# tick-mk-4_1.net
KiCad netlist of a schematic drawn in EAGLE
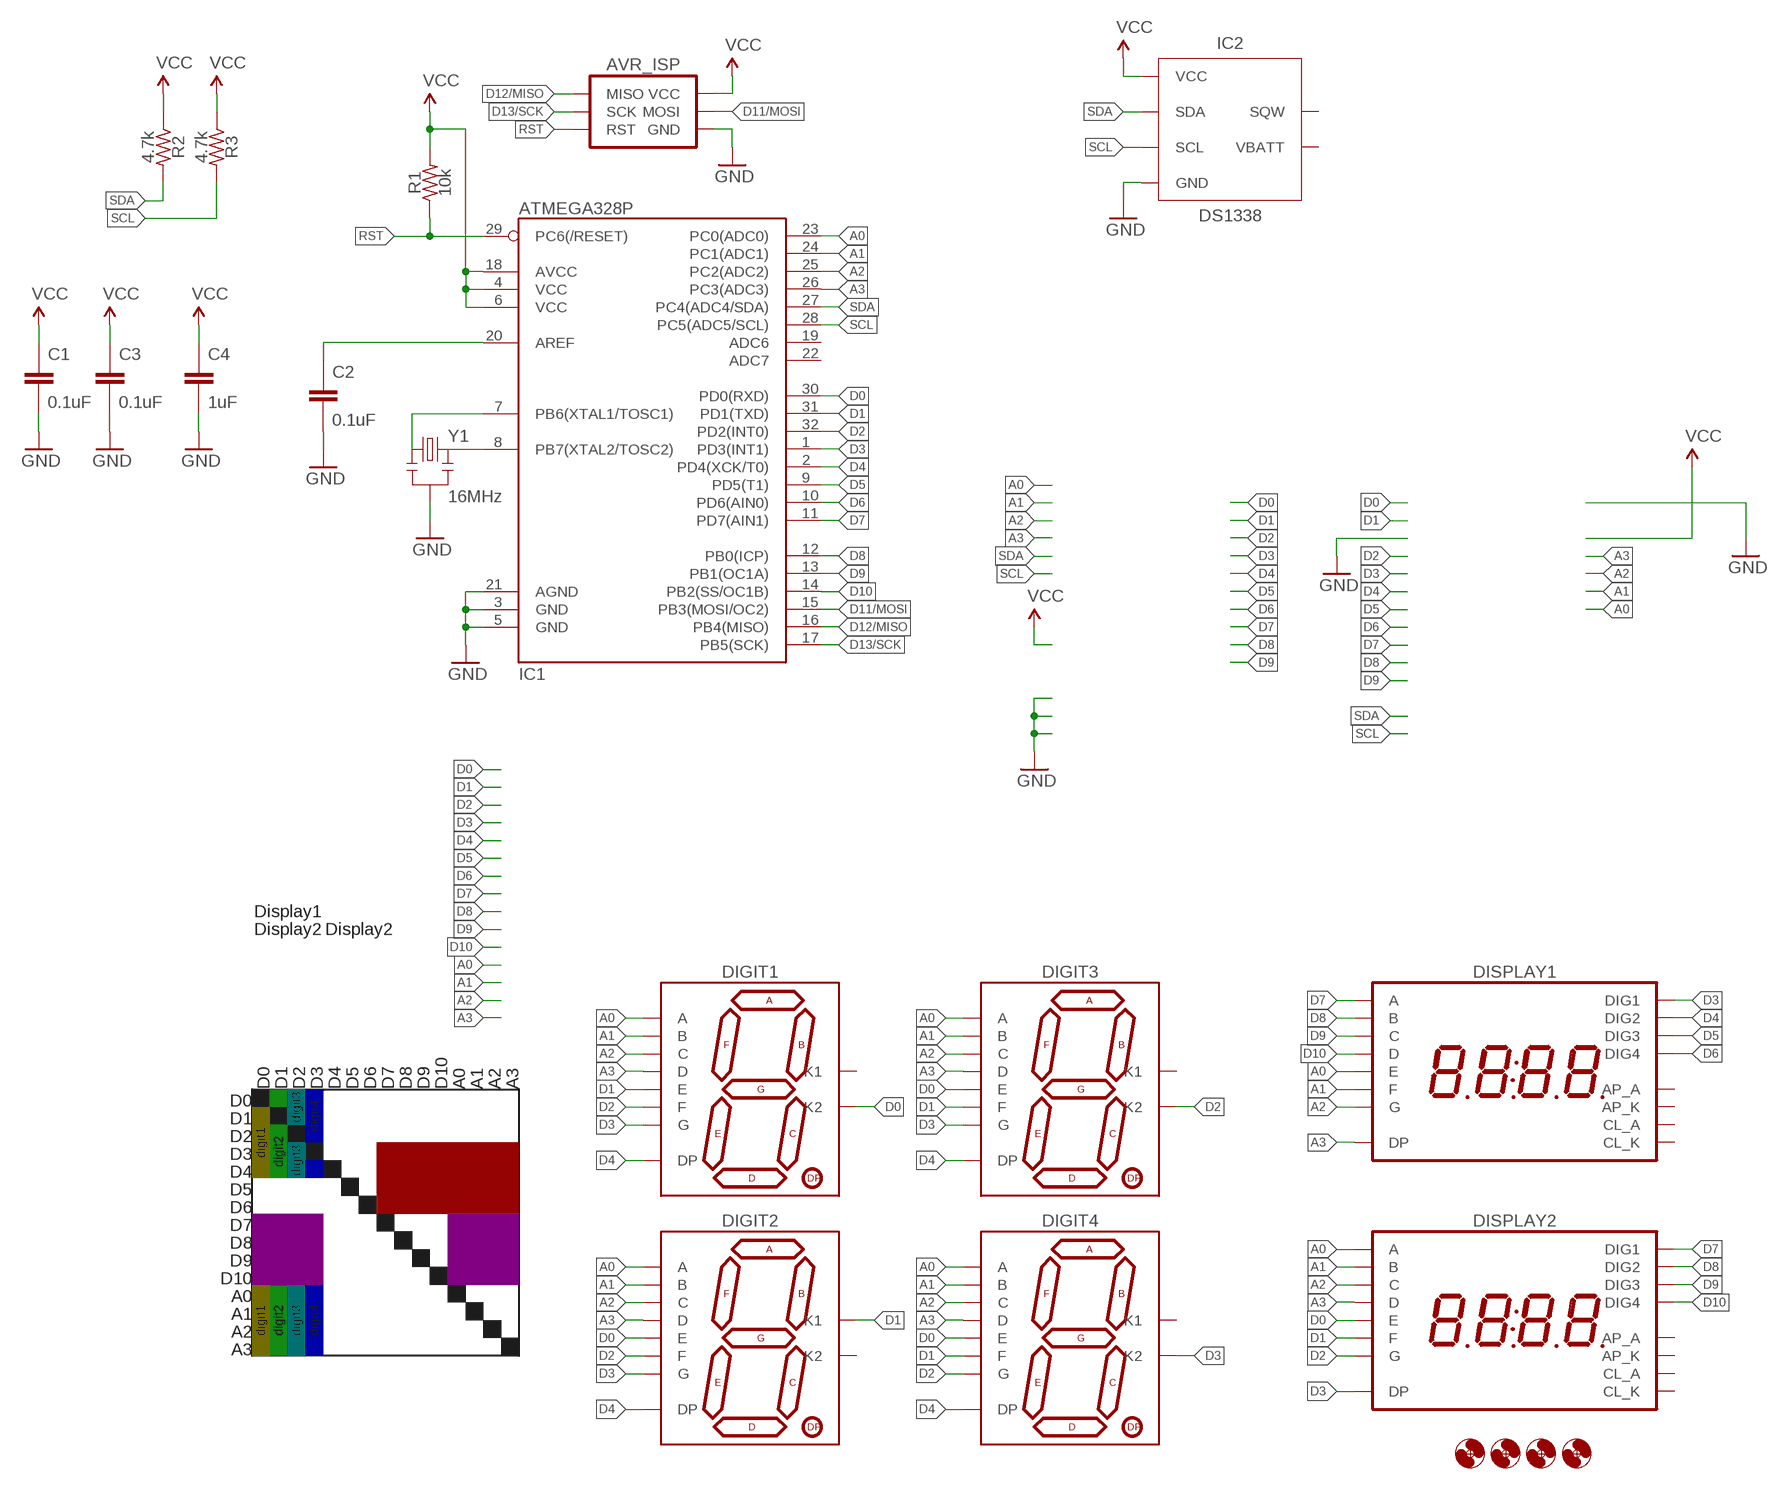
[diagram p0: schematic, sheet 1]

(export (version "E")
  (design (tool "Eeschema 10.0.6"))
  (components
    (comp (ref "AVR_ISP")
      (value "AVR_SPI_PRG_6PTH")
      (footprint "eagle-import:2X3")
      (libsource (lib "eagle-import") (part "AVR_SPI_PRG_6PTH"))
    )
    (comp (ref "C1")
      (value "0.1uF")
      (footprint "eagle-import:C0805")
      (libsource (lib "eagle-import") (part "CAPACITOR-CERAMICC0805"))
    )
    (comp (ref "C2")
      (value "0.1uF")
      (footprint "eagle-import:C0805")
      (libsource (lib "eagle-import") (part "CAPACITOR-CERAMICC0805"))
    )
    (comp (ref "C3")
      (value "0.1uF")
      (footprint "eagle-import:C0805")
      (libsource (lib "eagle-import") (part "CAPACITOR-CERAMICC0805"))
    )
    (comp (ref "C4")
      (value "1uF")
      (footprint "eagle-import:C0805")
      (libsource (lib "eagle-import") (part "CAPACITOR-CERAMICC0805"))
    )
    (comp (ref "DIGIT1")
      (value "7SEG_1DIGPTH-25.4MM")
      (footprint "eagle-import:7SEG_1DIG_25.4MM")
      (libsource (lib "eagle-import") (part "7SEG_1DIGPTH-25.4MM"))
    )
    (comp (ref "DIGIT2")
      (value "7SEG_1DIGPTH-25.4MM")
      (footprint "eagle-import:7SEG_1DIG_25.4MM")
      (libsource (lib "eagle-import") (part "7SEG_1DIGPTH-25.4MM"))
    )
    (comp (ref "DIGIT3")
      (value "7SEG_1DIGPTH-25.4MM")
      (footprint "eagle-import:7SEG_1DIG_25.4MM")
      (libsource (lib "eagle-import") (part "7SEG_1DIGPTH-25.4MM"))
    )
    (comp (ref "DIGIT4")
      (value "7SEG_1DIGPTH-25.4MM")
      (footprint "eagle-import:7SEG_1DIG_25.4MM")
      (libsource (lib "eagle-import") (part "7SEG_1DIGPTH-25.4MM"))
    )
    (comp (ref "DISPLAY1")
      (value "7SEG_4DIGIT_COLON_APOS")
      (footprint "eagle-import:7SEG_4DIG_10MM")
      (libsource (lib "eagle-import") (part "7SEG_4DIGIT_COLON_APOS"))
    )
    (comp (ref "DISPLAY2")
      (value "7SEG_4DIGIT_COLON_APOS")
      (footprint "eagle-import:7SEG_4DIG_10MM")
      (libsource (lib "eagle-import") (part "7SEG_4DIGIT_COLON_APOS"))
    )
    (comp (ref "H1")
      (value "HOLE#2")
      (footprint "eagle-import:HOLE-#2")
      (libsource (lib "eagle-import") (part "HOLE#2"))
    )
    (comp (ref "H2")
      (value "HOLE#2")
      (footprint "eagle-import:HOLE-#2")
      (libsource (lib "eagle-import") (part "HOLE#2"))
    )
    (comp (ref "H3")
      (value "HOLE#2")
      (footprint "eagle-import:HOLE-#2")
      (libsource (lib "eagle-import") (part "HOLE#2"))
    )
    (comp (ref "H4")
      (value "HOLE#2")
      (footprint "eagle-import:HOLE-#2")
      (libsource (lib "eagle-import") (part "HOLE#2"))
    )
    (comp (ref "IC1")
      (value "ATMEGA328P")
      (footprint "eagle-import:TQFP32-08")
      (libsource (lib "eagle-import") (part "ATMEGA328_SMT"))
    )
    (comp (ref "IC2")
      (value "DS1338")
      (footprint "eagle-import:SO16W")
      (libsource (lib "eagle-import") (part "DS1338CSOIC16W"))
    )
    (comp (ref "R1")
      (value "10k")
      (footprint "eagle-import:R0805")
      (libsource (lib "eagle-import") (part "RESISTORR0805"))
    )
    (comp (ref "R2")
      (value "4.7k")
      (footprint "eagle-import:R0805")
      (libsource (lib "eagle-import") (part "RESISTORR0805"))
    )
    (comp (ref "R3")
      (value "4.7k")
      (footprint "eagle-import:R0805")
      (libsource (lib "eagle-import") (part "RESISTORR0805"))
    )
    (comp (ref "Y1")
      (value "16MHz")
      (footprint "eagle-import:RESONATOR-4.7X4.1X1.2MM")
      (libsource (lib "eagle-import") (part "RESONATORSMD-4.7X4.1X1.2"))
    )
  )
  (nets
    (net (code "1") (name "A0") (class "Default")
      (node (ref "DIGIT1") (pin "7") (pinfunction "A_7") (pintype "bidirectional"))
      (node (ref "DIGIT2") (pin "7") (pinfunction "A_7") (pintype "bidirectional"))
      (node (ref "DIGIT3") (pin "7") (pinfunction "A_7") (pintype "bidirectional"))
      (node (ref "DIGIT4") (pin "7") (pinfunction "A_7") (pintype "bidirectional"))
      (node (ref "DISPLAY1") (pin "5") (pinfunction "E_5") (pintype "passive"))
      (node (ref "DISPLAY2") (pin "14") (pinfunction "A_14") (pintype "passive"))
      (node (ref "IC1") (pin "23") (pinfunction "PC0(ADC0)_23") (pintype "bidirectional"))
    )
    (net (code "2") (name "A1") (class "Default")
      (node (ref "DIGIT1") (pin "6") (pinfunction "B_6") (pintype "bidirectional"))
      (node (ref "DIGIT2") (pin "6") (pinfunction "B_6") (pintype "bidirectional"))
      (node (ref "DIGIT3") (pin "6") (pinfunction "B_6") (pintype "bidirectional"))
      (node (ref "DIGIT4") (pin "6") (pinfunction "B_6") (pintype "bidirectional"))
      (node (ref "DISPLAY1") (pin "11") (pinfunction "F_11") (pintype "passive"))
      (node (ref "DISPLAY2") (pin "16") (pinfunction "B_16") (pintype "passive"))
      (node (ref "IC1") (pin "24") (pinfunction "PC1(ADC1)_24") (pintype "bidirectional"))
    )
    (net (code "3") (name "A2") (class "Default")
      (node (ref "DIGIT1") (pin "4") (pinfunction "C_4") (pintype "bidirectional"))
      (node (ref "DIGIT2") (pin "4") (pinfunction "C_4") (pintype "bidirectional"))
      (node (ref "DIGIT3") (pin "4") (pinfunction "C_4") (pintype "bidirectional"))
      (node (ref "DIGIT4") (pin "4") (pinfunction "C_4") (pintype "bidirectional"))
      (node (ref "DISPLAY1") (pin "15") (pinfunction "G_15") (pintype "passive"))
      (node (ref "DISPLAY2") (pin "13") (pinfunction "C_13") (pintype "passive"))
      (node (ref "IC1") (pin "25") (pinfunction "PC2(ADC2)_25") (pintype "bidirectional"))
    )
    (net (code "4") (name "A3") (class "Default")
      (node (ref "DIGIT1") (pin "2") (pinfunction "D_2") (pintype "bidirectional"))
      (node (ref "DIGIT2") (pin "2") (pinfunction "D_2") (pintype "bidirectional"))
      (node (ref "DIGIT3") (pin "2") (pinfunction "D_2") (pintype "bidirectional"))
      (node (ref "DIGIT4") (pin "2") (pinfunction "D_2") (pintype "bidirectional"))
      (node (ref "DISPLAY1") (pin "7") (pinfunction "DP_7") (pintype "passive"))
      (node (ref "DISPLAY2") (pin "3") (pinfunction "D_3") (pintype "passive"))
      (node (ref "IC1") (pin "26") (pinfunction "PC3(ADC3)_26") (pintype "bidirectional"))
    )
    (net (code "5") (name "D0") (class "Default")
      (node (ref "DIGIT1") (pin "8") (pinfunction "K2_8") (pintype "bidirectional"))
      (node (ref "DIGIT2") (pin "1") (pinfunction "E_1") (pintype "bidirectional"))
      (node (ref "DIGIT3") (pin "1") (pinfunction "E_1") (pintype "bidirectional"))
      (node (ref "DIGIT4") (pin "1") (pinfunction "E_1") (pintype "bidirectional"))
      (node (ref "DISPLAY2") (pin "5") (pinfunction "E_5") (pintype "passive"))
      (node (ref "IC1") (pin "30") (pinfunction "PD0(RXD)_30") (pintype "bidirectional"))
    )
    (net (code "6") (name "D1") (class "Default")
      (node (ref "DIGIT1") (pin "1") (pinfunction "E_1") (pintype "bidirectional"))
      (node (ref "DIGIT2") (pin "3") (pinfunction "K1_3") (pintype "bidirectional"))
      (node (ref "DIGIT3") (pin "9") (pinfunction "F_9") (pintype "bidirectional"))
      (node (ref "DIGIT4") (pin "9") (pinfunction "F_9") (pintype "bidirectional"))
      (node (ref "DISPLAY2") (pin "11") (pinfunction "F_11") (pintype "passive"))
      (node (ref "IC1") (pin "31") (pinfunction "PD1(TXD)_31") (pintype "bidirectional"))
    )
    (net (code "7") (name "D2") (class "Default")
      (node (ref "DIGIT1") (pin "9") (pinfunction "F_9") (pintype "bidirectional"))
      (node (ref "DIGIT2") (pin "9") (pinfunction "F_9") (pintype "bidirectional"))
      (node (ref "DIGIT3") (pin "8") (pinfunction "K2_8") (pintype "bidirectional"))
      (node (ref "DIGIT4") (pin "10") (pinfunction "G_10") (pintype "bidirectional"))
      (node (ref "DISPLAY2") (pin "15") (pinfunction "G_15") (pintype "passive"))
      (node (ref "IC1") (pin "32") (pinfunction "PD2(INT0)_32") (pintype "bidirectional"))
    )
    (net (code "8") (name "D3") (class "Default")
      (node (ref "DIGIT1") (pin "10") (pinfunction "G_10") (pintype "bidirectional"))
      (node (ref "DIGIT2") (pin "10") (pinfunction "G_10") (pintype "bidirectional"))
      (node (ref "DIGIT3") (pin "10") (pinfunction "G_10") (pintype "bidirectional"))
      (node (ref "DIGIT4") (pin "8") (pinfunction "K2_8") (pintype "bidirectional"))
      (node (ref "DISPLAY1") (pin "1") (pinfunction "DIG1_1") (pintype "passive"))
      (node (ref "DISPLAY2") (pin "7") (pinfunction "DP_7") (pintype "passive"))
      (node (ref "IC1") (pin "1") (pinfunction "PD3(INT1)_1") (pintype "bidirectional"))
    )
    (net (code "9") (name "D4") (class "Default")
      (node (ref "DIGIT1") (pin "5") (pinfunction "DP_5") (pintype "bidirectional"))
      (node (ref "DIGIT2") (pin "5") (pinfunction "DP_5") (pintype "bidirectional"))
      (node (ref "DIGIT3") (pin "5") (pinfunction "DP_5") (pintype "bidirectional"))
      (node (ref "DIGIT4") (pin "5") (pinfunction "DP_5") (pintype "bidirectional"))
      (node (ref "DISPLAY1") (pin "2") (pinfunction "DIG2_2") (pintype "passive"))
      (node (ref "IC1") (pin "2") (pinfunction "PD4(XCK/T0)_2") (pintype "bidirectional"))
    )
    (net (code "10") (name "D5") (class "Default")
      (node (ref "DISPLAY1") (pin "6") (pinfunction "DIG3_6") (pintype "passive"))
      (node (ref "IC1") (pin "9") (pinfunction "PD5(T1)_9") (pintype "bidirectional"))
    )
    (net (code "11") (name "D6") (class "Default")
      (node (ref "DISPLAY1") (pin "8") (pinfunction "DIG4_8") (pintype "passive"))
      (node (ref "IC1") (pin "10") (pinfunction "PD6(AIN0)_10") (pintype "bidirectional"))
    )
    (net (code "12") (name "D7") (class "Default")
      (node (ref "DISPLAY1") (pin "14") (pinfunction "A_14") (pintype "passive"))
      (node (ref "DISPLAY2") (pin "1") (pinfunction "DIG1_1") (pintype "passive"))
      (node (ref "IC1") (pin "11") (pinfunction "PD7(AIN1)_11") (pintype "bidirectional"))
    )
    (net (code "13") (name "D8") (class "Default")
      (node (ref "DISPLAY1") (pin "16") (pinfunction "B_16") (pintype "passive"))
      (node (ref "DISPLAY2") (pin "2") (pinfunction "DIG2_2") (pintype "passive"))
      (node (ref "IC1") (pin "12") (pinfunction "PB0(ICP)_12") (pintype "bidirectional"))
    )
    (net (code "14") (name "D9") (class "Default")
      (node (ref "DISPLAY1") (pin "13") (pinfunction "C_13") (pintype "passive"))
      (node (ref "DISPLAY2") (pin "6") (pinfunction "DIG3_6") (pintype "passive"))
      (node (ref "IC1") (pin "13") (pinfunction "PB1(OC1A)_13") (pintype "bidirectional"))
    )
    (net (code "15") (name "D10") (class "Default")
      (node (ref "DISPLAY1") (pin "3") (pinfunction "D_3") (pintype "passive"))
      (node (ref "DISPLAY2") (pin "8") (pinfunction "DIG4_8") (pintype "passive"))
      (node (ref "IC1") (pin "14") (pinfunction "PB2(SS/OC1B)_14") (pintype "bidirectional"))
    )
    (net (code "16") (name "D11{slash}MOSI") (class "Default")
      (node (ref "AVR_ISP") (pin "4") (pinfunction "MOSI_4") (pintype "passive"))
      (node (ref "IC1") (pin "15") (pinfunction "PB3(MOSI/OC2)_15") (pintype "bidirectional"))
    )
    (net (code "17") (name "D12{slash}MISO") (class "Default")
      (node (ref "AVR_ISP") (pin "1") (pinfunction "MISO_1") (pintype "passive"))
      (node (ref "IC1") (pin "16") (pinfunction "PB4(MISO)_16") (pintype "bidirectional"))
    )
    (net (code "18") (name "D13{slash}SCK") (class "Default")
      (node (ref "AVR_ISP") (pin "3") (pinfunction "SCK_3") (pintype "passive"))
      (node (ref "IC1") (pin "17") (pinfunction "PB5(SCK)_17") (pintype "bidirectional"))
    )
    (net (code "19") (name "GND") (class "Default")
      (node (ref "AVR_ISP") (pin "6") (pinfunction "GND_6") (pintype "passive"))
      (node (ref "C1") (pin "2") (pinfunction "2_2") (pintype "passive"))
      (node (ref "C2") (pin "2") (pinfunction "2_2") (pintype "passive"))
      (node (ref "C3") (pin "2") (pinfunction "2_2") (pintype "passive"))
      (node (ref "C4") (pin "2") (pinfunction "2_2") (pintype "passive"))
      (node (ref "IC1") (pin "21") (pinfunction "AGND_21") (pintype "bidirectional"))
      (node (ref "IC1") (pin "3") (pinfunction "GND_3") (pintype "bidirectional"))
      (node (ref "IC1") (pin "5") (pinfunction "GND_5") (pintype "bidirectional"))
      (node (ref "IC2") (pin "10") (pinfunction "GND_10") (pintype "bidirectional"))
      (node (ref "IC2") (pin "11") (pinfunction "GND_11") (pintype "bidirectional"))
      (node (ref "IC2") (pin "12") (pinfunction "GND_12") (pintype "bidirectional"))
      (node (ref "IC2") (pin "13") (pinfunction "GND_13") (pintype "bidirectional"))
      (node (ref "IC2") (pin "15") (pinfunction "GND_15") (pintype "bidirectional"))
      (node (ref "IC2") (pin "4") (pinfunction "GND_4") (pintype "bidirectional"))
      (node (ref "IC2") (pin "5") (pinfunction "GND_5") (pintype "bidirectional"))
      (node (ref "IC2") (pin "6") (pinfunction "GND_6") (pintype "bidirectional"))
      (node (ref "IC2") (pin "7") (pinfunction "GND_7") (pintype "bidirectional"))
      (node (ref "IC2") (pin "8") (pinfunction "GND_8") (pintype "bidirectional"))
      (node (ref "IC2") (pin "9") (pinfunction "GND_9") (pintype "bidirectional"))
      (node (ref "Y1") (pin "2") (pinfunction "2_2") (pintype "passive"))
    )
    (net (code "20") (name "Net-(IC1-AREF)") (class "Default")
      (node (ref "C2") (pin "1") (pinfunction "1_1") (pintype "passive"))
      (node (ref "IC1") (pin "20") (pinfunction "AREF_20") (pintype "bidirectional"))
    )
    (net (code "21") (name "Net-(IC1-PB6(XTAL1{slash}TOSC1))") (class "Default")
      (node (ref "IC1") (pin "7") (pinfunction "PB6(XTAL1/TOSC1)_7") (pintype "bidirectional"))
      (node (ref "Y1") (pin "1") (pinfunction "1_1") (pintype "passive"))
    )
    (net (code "22") (name "Net-(IC1-PB7(XTAL2{slash}TOSC2))") (class "Default")
      (node (ref "IC1") (pin "8") (pinfunction "PB7(XTAL2/TOSC2)_8") (pintype "bidirectional"))
      (node (ref "Y1") (pin "3") (pinfunction "3_3") (pintype "passive"))
    )
    (net (code "23") (name "RST") (class "Default")
      (node (ref "AVR_ISP") (pin "5") (pinfunction "RST_5") (pintype "passive"))
      (node (ref "IC1") (pin "29") (pinfunction "PC6(/RESET)_29") (pintype "bidirectional"))
      (node (ref "R1") (pin "1") (pinfunction "1_1") (pintype "passive"))
    )
    (net (code "24") (name "SCL") (class "Default")
      (node (ref "IC1") (pin "28") (pinfunction "PC5(ADC5/SCL)_28") (pintype "bidirectional"))
      (node (ref "IC2") (pin "1") (pinfunction "SCL_1") (pintype "bidirectional"))
      (node (ref "R3") (pin "2") (pinfunction "2_2") (pintype "passive"))
    )
    (net (code "25") (name "SDA") (class "Default")
      (node (ref "IC1") (pin "27") (pinfunction "PC4(ADC4/SDA)_27") (pintype "bidirectional"))
      (node (ref "IC2") (pin "16") (pinfunction "SDA_16") (pintype "bidirectional"))
      (node (ref "R2") (pin "2") (pinfunction "2_2") (pintype "passive"))
    )
    (net (code "26") (name "VCC") (class "Default")
      (node (ref "AVR_ISP") (pin "2") (pinfunction "VCC_2") (pintype "passive"))
      (node (ref "C1") (pin "1") (pinfunction "1_1") (pintype "passive"))
      (node (ref "C3") (pin "1") (pinfunction "1_1") (pintype "passive"))
      (node (ref "C4") (pin "1") (pinfunction "1_1") (pintype "passive"))
      (node (ref "IC1") (pin "18") (pinfunction "AVCC_18") (pintype "bidirectional"))
      (node (ref "IC1") (pin "4") (pinfunction "VCC_4") (pintype "bidirectional"))
      (node (ref "IC1") (pin "6") (pinfunction "VCC_6") (pintype "bidirectional"))
      (node (ref "IC2") (pin "3") (pinfunction "VCC_3") (pintype "bidirectional"))
      (node (ref "R1") (pin "2") (pinfunction "2_2") (pintype "passive"))
      (node (ref "R2") (pin "1") (pinfunction "1_1") (pintype "passive"))
      (node (ref "R3") (pin "1") (pinfunction "1_1") (pintype "passive"))
    )
    (net (code "27") (name "unconnected-(DIGIT1-K1-Pad3)") (class "Default")
      (node (ref "DIGIT1") (pin "3") (pinfunction "K1_3") (pintype "bidirectional"))
    )
    (net (code "28") (name "unconnected-(DIGIT2-K2-Pad8)") (class "Default")
      (node (ref "DIGIT2") (pin "8") (pinfunction "K2_8") (pintype "bidirectional"))
    )
    (net (code "29") (name "unconnected-(DIGIT3-K1-Pad3)") (class "Default")
      (node (ref "DIGIT3") (pin "3") (pinfunction "K1_3") (pintype "bidirectional"))
    )
    (net (code "30") (name "unconnected-(DIGIT4-K1-Pad3)") (class "Default")
      (node (ref "DIGIT4") (pin "3") (pinfunction "K1_3") (pintype "bidirectional"))
    )
    (net (code "31") (name "unconnected-(DISPLAY1-AP_A-Pad10)") (class "Default")
      (node (ref "DISPLAY1") (pin "10") (pinfunction "AP_A_10") (pintype "bidirectional"))
    )
    (net (code "32") (name "unconnected-(DISPLAY1-AP_K-Pad9)") (class "Default")
      (node (ref "DISPLAY1") (pin "9") (pinfunction "AP_K_9") (pintype "bidirectional"))
    )
    (net (code "33") (name "unconnected-(DISPLAY1-CL_A-Pad4)") (class "Default")
      (node (ref "DISPLAY1") (pin "4") (pinfunction "CL_A_4") (pintype "passive"))
    )
    (net (code "34") (name "unconnected-(DISPLAY1-CL_K-Pad12)") (class "Default")
      (node (ref "DISPLAY1") (pin "12") (pinfunction "CL_K_12") (pintype "passive"))
    )
    (net (code "35") (name "unconnected-(DISPLAY2-AP_A-Pad10)") (class "Default")
      (node (ref "DISPLAY2") (pin "10") (pinfunction "AP_A_10") (pintype "bidirectional"))
    )
    (net (code "36") (name "unconnected-(DISPLAY2-AP_K-Pad9)") (class "Default")
      (node (ref "DISPLAY2") (pin "9") (pinfunction "AP_K_9") (pintype "bidirectional"))
    )
    (net (code "37") (name "unconnected-(DISPLAY2-CL_A-Pad4)") (class "Default")
      (node (ref "DISPLAY2") (pin "4") (pinfunction "CL_A_4") (pintype "passive"))
    )
    (net (code "38") (name "unconnected-(DISPLAY2-CL_K-Pad12)") (class "Default")
      (node (ref "DISPLAY2") (pin "12") (pinfunction "CL_K_12") (pintype "passive"))
    )
    (net (code "39") (name "unconnected-(IC1-ADC6-Pad19)") (class "Default")
      (node (ref "IC1") (pin "19") (pinfunction "ADC6_19") (pintype "bidirectional"))
    )
    (net (code "40") (name "unconnected-(IC1-ADC7-Pad22)") (class "Default")
      (node (ref "IC1") (pin "22") (pinfunction "ADC7_22") (pintype "bidirectional"))
    )
    (net (code "41") (name "unconnected-(IC2-SQW-Pad2)") (class "Default")
      (node (ref "IC2") (pin "2") (pinfunction "SQW_2") (pintype "bidirectional"))
    )
    (net (code "42") (name "unconnected-(IC2-VBATT-Pad14)") (class "Default")
      (node (ref "IC2") (pin "14") (pinfunction "VBATT_14") (pintype "bidirectional"))
    )
  )
)
